# Touch_MediumWheel.net
KiCad netlist of a schematic drawn in Altium Designer
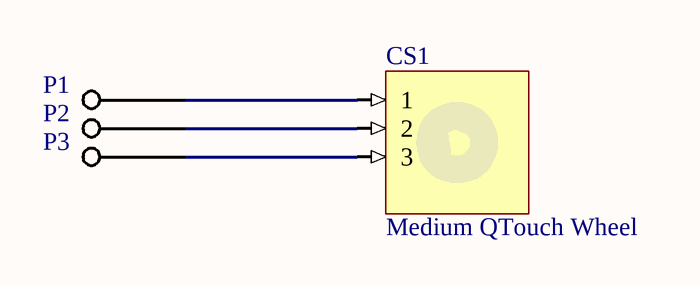
[diagram p0: Touch_MediumWheel.SchDoc]

(export (version "E")
  (design (tool "Eeschema 10.0.6"))
  (components
    (comp (ref "CS1")
      (value "Medium QTouch Wheel")
      (libsource (lib "Atmel QTouch") (part "MediumQTouchWheel"))
    )
    (comp (ref "P1")
      (value "PAD_27x27MILS")
      (footprint "PAD_27x27MILS")
      (description "27 x 27 mils PAD connection")
      (libsource (lib "SmartHalo") (part "PAD_27x27MILS"))
    )
    (comp (ref "P2")
      (value "PAD_27x27MILS")
      (footprint "PAD_27x27MILS")
      (description "27 x 27 mils PAD connection")
      (libsource (lib "SmartHalo") (part "PAD_27x27MILS"))
    )
    (comp (ref "P3")
      (value "PAD_27x27MILS")
      (footprint "PAD_27x27MILS")
      (description "27 x 27 mils PAD connection")
      (libsource (lib "SmartHalo") (part "PAD_27x27MILS"))
    )
  )
  (nets
    (net (code "1") (name "Net-(CS1-Pad1)") (class "Default")
      (node (ref "CS1") (pin "1") (pinfunction "1_1") (pintype "input"))
      (node (ref "P1") (pin "1") (pinfunction "1_1") (pintype "passive"))
    )
    (net (code "2") (name "Net-(CS1-Pad2)") (class "Default")
      (node (ref "CS1") (pin "2") (pinfunction "2_2") (pintype "input"))
      (node (ref "P2") (pin "1") (pinfunction "1_1") (pintype "passive"))
    )
    (net (code "3") (name "Net-(CS1-Pad3)") (class "Default")
      (node (ref "CS1") (pin "3") (pinfunction "3_3") (pintype "input"))
      (node (ref "P3") (pin "1") (pinfunction "1_1") (pintype "passive"))
    )
  )
)
